# controllerRev1.net
KiCad netlist of a schematic drawn in EAGLE
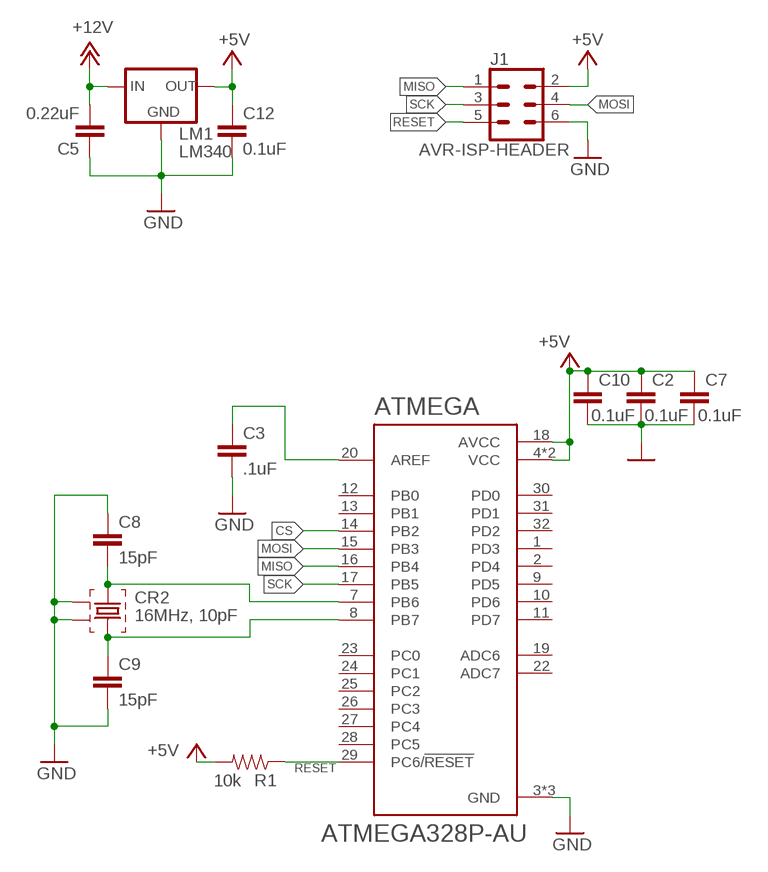
[diagram p0: schematic, sheet 1]

(export (version "E")
  (design (tool "Eeschema 10.0.6"))
  (components
    (comp (ref "ATMEGA")
      (value "ATMEGA328P-AU")
      (footprint "eagle-import:QFP80P900X900X120-32N")
      (fields (field (name "MF") "Microchip"))
      (libsource (lib "eagle-import") (part "ATMEGA328P-AU"))
    )
    (comp (ref "C2")
      (value "0.1uF")
      (footprint "eagle-import:0603-CAP")
      (libsource (lib "eagle-import") (part "CAP0603-CAP"))
    )
    (comp (ref "C3")
      (value ".1uF")
      (footprint "eagle-import:0603-CAP")
      (libsource (lib "eagle-import") (part "CAP0603-CAP"))
    )
    (comp (ref "C5")
      (value "0.22uF")
      (footprint "eagle-import:0603-CAP")
      (libsource (lib "eagle-import") (part "CAP0603-CAP"))
    )
    (comp (ref "C7")
      (value "0.1uF")
      (footprint "eagle-import:0603-CAP")
      (libsource (lib "eagle-import") (part "CAP0603-CAP"))
    )
    (comp (ref "C8")
      (value "15pF")
      (footprint "eagle-import:0603-CAP")
      (libsource (lib "eagle-import") (part "CAP0603-CAP"))
    )
    (comp (ref "C9")
      (value "15pF")
      (footprint "eagle-import:0603-CAP")
      (libsource (lib "eagle-import") (part "CAP0603-CAP"))
    )
    (comp (ref "C10")
      (value "0.1uF")
      (footprint "eagle-import:0603-CAP")
      (libsource (lib "eagle-import") (part "CAP0603-CAP"))
    )
    (comp (ref "C12")
      (value "0.1uF")
      (footprint "eagle-import:0603-CAP")
      (libsource (lib "eagle-import") (part "CAP0603-CAP"))
    )
    (comp (ref "CR2")
      (value "16MHz, 10pF")
      (footprint "eagle-import:ABM3B")
      (libsource (lib "eagle-import") (part "ABM3B"))
    )
    (comp (ref "J1")
      (value "AVR-ISP-HEADER")
      (footprint "eagle-import:2X03")
      (libsource (lib "eagle-import") (part "AVR-ISP-HEADER"))
    )
    (comp (ref "LM1")
      (value "LM340")
      (footprint "eagle-import:SOT223")
      (libsource (lib "eagle-import") (part "LM340"))
    )
    (comp (ref "R1")
      (value "10k")
      (footprint "eagle-import:0603-RES")
      (libsource (lib "eagle-import") (part "RESISTOR0603"))
    )
  )
  (nets
    (net (code "1") (name "+5V") (class "Default")
      (node (ref "ATMEGA") (pin "18") (pinfunction "AVCC_18") (pintype "power_in"))
      (node (ref "ATMEGA") (pin "4") (pinfunction "VCC_4") (pintype "power_in"))
      (node (ref "ATMEGA") (pin "6") (pinfunction "VCC_6") (pintype "power_in"))
      (node (ref "C10") (pin "1") (pinfunction "1_1") (pintype "passive"))
      (node (ref "C12") (pin "1") (pinfunction "1_1") (pintype "passive"))
      (node (ref "C2") (pin "1") (pinfunction "1_1") (pintype "passive"))
      (node (ref "C7") (pin "1") (pinfunction "1_1") (pintype "passive"))
      (node (ref "J1") (pin "2") (pinfunction "2_2") (pintype "passive"))
      (node (ref "LM1") (pin "3") (pinfunction "OUT_3") (pintype "output"))
      (node (ref "R1") (pin "2") (pinfunction "2_2") (pintype "passive"))
    )
    (net (code "2") (name "+12V") (class "Default")
      (node (ref "C5") (pin "2") (pinfunction "2_2") (pintype "passive"))
      (node (ref "LM1") (pin "1") (pinfunction "IN_1") (pintype "input"))
    )
    (net (code "3") (name "CS") (class "Default")
      (node (ref "ATMEGA") (pin "14") (pinfunction "PB2_14") (pintype "bidirectional"))
    )
    (net (code "4") (name "GND") (class "Default")
      (node (ref "ATMEGA") (pin "21") (pinfunction "GND_21") (pintype "power_in"))
      (node (ref "ATMEGA") (pin "3") (pinfunction "GND_3") (pintype "power_in"))
      (node (ref "ATMEGA") (pin "5") (pinfunction "GND_5") (pintype "power_in"))
      (node (ref "C10") (pin "2") (pinfunction "2_2") (pintype "passive"))
      (node (ref "C12") (pin "2") (pinfunction "2_2") (pintype "passive"))
      (node (ref "C2") (pin "2") (pinfunction "2_2") (pintype "passive"))
      (node (ref "C3") (pin "2") (pinfunction "2_2") (pintype "passive"))
      (node (ref "C5") (pin "1") (pinfunction "1_1") (pintype "passive"))
      (node (ref "C7") (pin "2") (pinfunction "2_2") (pintype "passive"))
      (node (ref "C8") (pin "1") (pinfunction "1_1") (pintype "passive"))
      (node (ref "C9") (pin "2") (pinfunction "2_2") (pintype "passive"))
      (node (ref "CR2") (pin "GND") (pinfunction "GND_GND") (pintype "passive"))
      (node (ref "CR2") (pin "GND2") (pinfunction "GND2_GND2") (pintype "passive"))
      (node (ref "J1") (pin "6") (pinfunction "6_6") (pintype "passive"))
      (node (ref "LM1") (pin "2") (pinfunction "GND_2") (pintype "input"))
      (node (ref "LM1") (pin "4") (pinfunction "GND_4") (pintype "input"))
    )
    (net (code "5") (name "MISO") (class "Default")
      (node (ref "ATMEGA") (pin "16") (pinfunction "PB4_16") (pintype "bidirectional"))
      (node (ref "J1") (pin "1") (pinfunction "1_1") (pintype "passive"))
    )
    (net (code "6") (name "MOSI") (class "Default")
      (node (ref "ATMEGA") (pin "15") (pinfunction "PB3_15") (pintype "bidirectional"))
      (node (ref "J1") (pin "4") (pinfunction "4_4") (pintype "passive"))
    )
    (net (code "7") (name "Net-(ATMEGA-AREF)") (class "Default")
      (node (ref "ATMEGA") (pin "20") (pinfunction "AREF_20") (pintype "input"))
      (node (ref "C3") (pin "1") (pinfunction "1_1") (pintype "passive"))
    )
    (net (code "8") (name "Net-(ATMEGA-PB6)") (class "Default")
      (node (ref "ATMEGA") (pin "7") (pinfunction "PB6_7") (pintype "bidirectional"))
      (node (ref "C8") (pin "2") (pinfunction "2_2") (pintype "passive"))
      (node (ref "CR2") (pin "1") (pinfunction "1_1") (pintype "passive"))
    )
    (net (code "9") (name "Net-(ATMEGA-PB7)") (class "Default")
      (node (ref "ATMEGA") (pin "8") (pinfunction "PB7_8") (pintype "bidirectional"))
      (node (ref "C9") (pin "1") (pinfunction "1_1") (pintype "passive"))
      (node (ref "CR2") (pin "3") (pinfunction "3_3") (pintype "passive"))
    )
    (net (code "10") (name "RESET") (class "Default")
      (node (ref "ATMEGA") (pin "29") (pinfunction "PC6/~{RESET}_29") (pintype "bidirectional"))
      (node (ref "J1") (pin "5") (pinfunction "5_5") (pintype "passive"))
      (node (ref "R1") (pin "1") (pinfunction "1_1") (pintype "passive"))
    )
    (net (code "11") (name "SCK") (class "Default")
      (node (ref "ATMEGA") (pin "17") (pinfunction "PB5_17") (pintype "bidirectional"))
      (node (ref "J1") (pin "3") (pinfunction "3_3") (pintype "passive"))
    )
    (net (code "12") (name "unconnected-(ATMEGA-ADC6-Pad19)") (class "Default")
      (node (ref "ATMEGA") (pin "19") (pinfunction "ADC6_19") (pintype "bidirectional"))
    )
    (net (code "13") (name "unconnected-(ATMEGA-ADC7-Pad22)") (class "Default")
      (node (ref "ATMEGA") (pin "22") (pinfunction "ADC7_22") (pintype "bidirectional"))
    )
    (net (code "14") (name "unconnected-(ATMEGA-PB0-Pad12)") (class "Default")
      (node (ref "ATMEGA") (pin "12") (pinfunction "PB0_12") (pintype "bidirectional"))
    )
    (net (code "15") (name "unconnected-(ATMEGA-PB1-Pad13)") (class "Default")
      (node (ref "ATMEGA") (pin "13") (pinfunction "PB1_13") (pintype "bidirectional"))
    )
    (net (code "16") (name "unconnected-(ATMEGA-PC0-Pad23)") (class "Default")
      (node (ref "ATMEGA") (pin "23") (pinfunction "PC0_23") (pintype "bidirectional"))
    )
    (net (code "17") (name "unconnected-(ATMEGA-PC1-Pad24)") (class "Default")
      (node (ref "ATMEGA") (pin "24") (pinfunction "PC1_24") (pintype "bidirectional"))
    )
    (net (code "18") (name "unconnected-(ATMEGA-PC2-Pad25)") (class "Default")
      (node (ref "ATMEGA") (pin "25") (pinfunction "PC2_25") (pintype "bidirectional"))
    )
    (net (code "19") (name "unconnected-(ATMEGA-PC3-Pad26)") (class "Default")
      (node (ref "ATMEGA") (pin "26") (pinfunction "PC3_26") (pintype "bidirectional"))
    )
    (net (code "20") (name "unconnected-(ATMEGA-PC4-Pad27)") (class "Default")
      (node (ref "ATMEGA") (pin "27") (pinfunction "PC4_27") (pintype "bidirectional"))
    )
    (net (code "21") (name "unconnected-(ATMEGA-PC5-Pad28)") (class "Default")
      (node (ref "ATMEGA") (pin "28") (pinfunction "PC5_28") (pintype "bidirectional"))
    )
    (net (code "22") (name "unconnected-(ATMEGA-PD0-Pad30)") (class "Default")
      (node (ref "ATMEGA") (pin "30") (pinfunction "PD0_30") (pintype "bidirectional"))
    )
    (net (code "23") (name "unconnected-(ATMEGA-PD1-Pad31)") (class "Default")
      (node (ref "ATMEGA") (pin "31") (pinfunction "PD1_31") (pintype "bidirectional"))
    )
    (net (code "24") (name "unconnected-(ATMEGA-PD2-Pad32)") (class "Default")
      (node (ref "ATMEGA") (pin "32") (pinfunction "PD2_32") (pintype "bidirectional"))
    )
    (net (code "25") (name "unconnected-(ATMEGA-PD3-Pad1)") (class "Default")
      (node (ref "ATMEGA") (pin "1") (pinfunction "PD3_1") (pintype "bidirectional"))
    )
    (net (code "26") (name "unconnected-(ATMEGA-PD4-Pad2)") (class "Default")
      (node (ref "ATMEGA") (pin "2") (pinfunction "PD4_2") (pintype "bidirectional"))
    )
    (net (code "27") (name "unconnected-(ATMEGA-PD5-Pad9)") (class "Default")
      (node (ref "ATMEGA") (pin "9") (pinfunction "PD5_9") (pintype "bidirectional"))
    )
    (net (code "28") (name "unconnected-(ATMEGA-PD6-Pad10)") (class "Default")
      (node (ref "ATMEGA") (pin "10") (pinfunction "PD6_10") (pintype "bidirectional"))
    )
    (net (code "29") (name "unconnected-(ATMEGA-PD7-Pad11)") (class "Default")
      (node (ref "ATMEGA") (pin "11") (pinfunction "PD7_11") (pintype "bidirectional"))
    )
  )
)
